# CURRENT_MEASURE_AC.net
KiCad netlist of a schematic drawn in Altium Designer
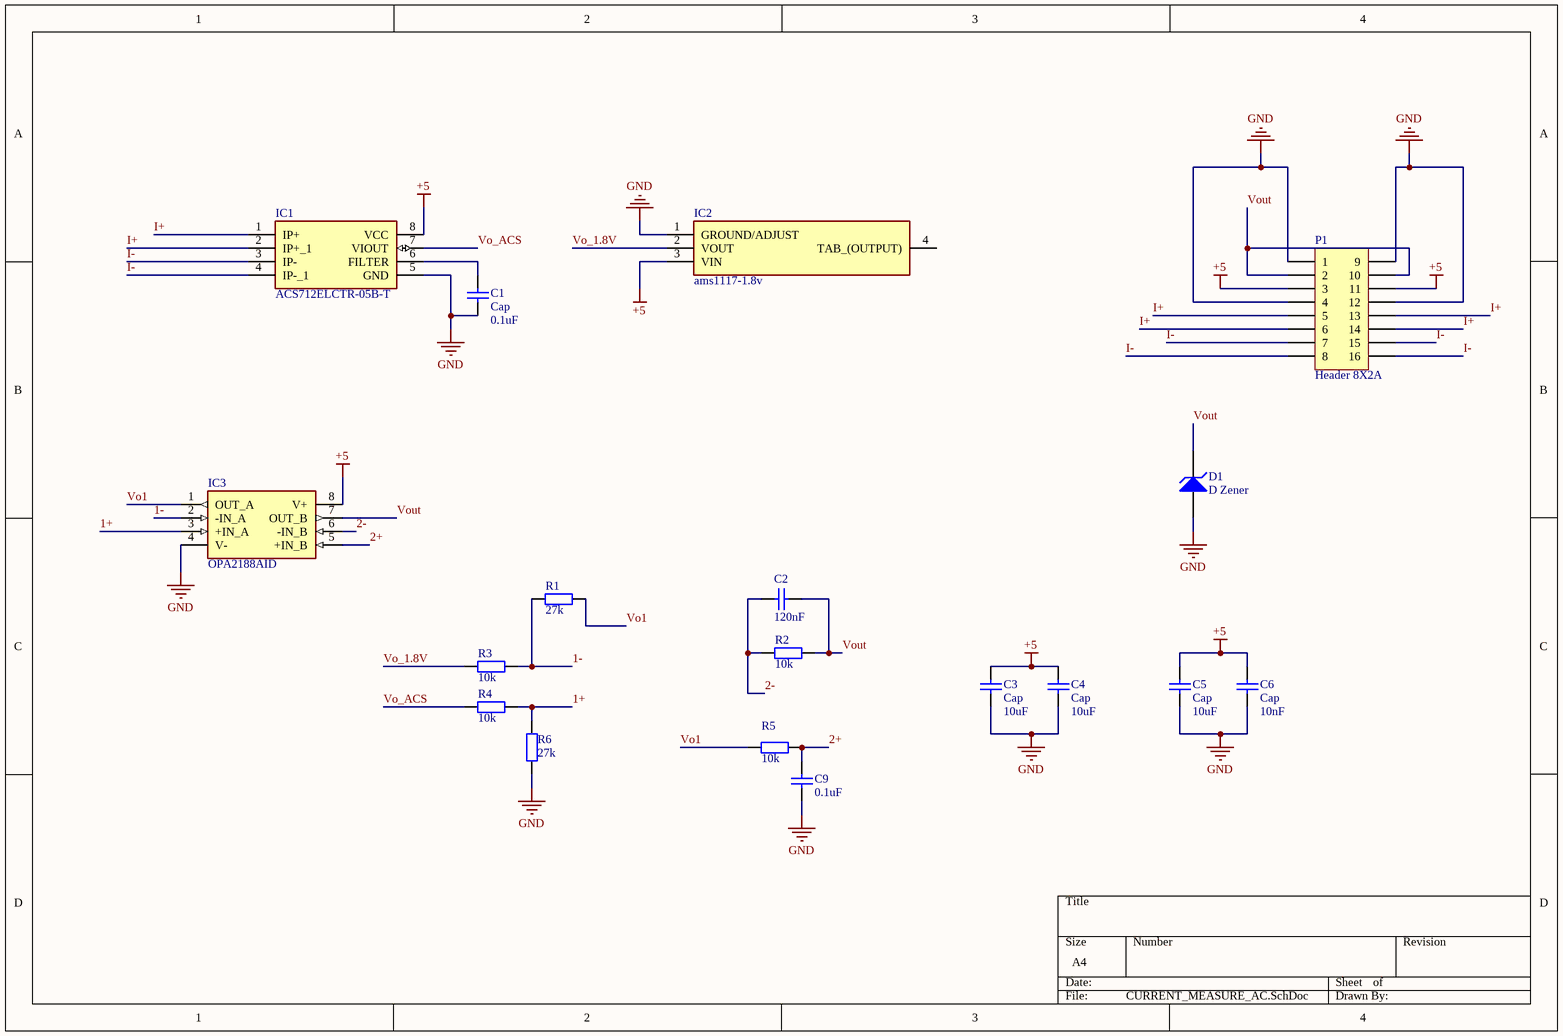
[diagram p0: CURRENT_MEASURE_AC.SchDoc]

(export (version "E")
  (design (tool "Eeschema 10.0.6"))
  (components
    (comp (ref "C1")
      (value "Cap")
      (footprint "1608[0603]")
      (description "Capacitor")
      (fields (field (name "ALTIUM_VALUE") "0.1uF") (field (name "PUBLISHER") "Altium Limited"))
      (libsource (lib "Miscellaneous Devices") (part "Cap"))
    )
    (comp (ref "C2")
      (value "120nF")
      (footprint "1608[0603]")
      (description "Capacitor")
      (fields (field (name "Comment") "Cap") (field (name "PUBLISHER") "Altium Limited"))
      (libsource (lib "Miscellaneous Devices") (part "Cap"))
    )
    (comp (ref "C3")
      (value "Cap")
      (footprint "1608[0603]")
      (description "Capacitor")
      (fields (field (name "ALTIUM_VALUE") "10uF") (field (name "PUBLISHER") "Altium Limited"))
      (libsource (lib "Miscellaneous Devices") (part "Cap"))
    )
    (comp (ref "C4")
      (value "Cap")
      (footprint "1608[0603]")
      (description "Capacitor")
      (fields (field (name "ALTIUM_VALUE") "10uF") (field (name "PUBLISHER") "Altium Limited"))
      (libsource (lib "Miscellaneous Devices") (part "Cap"))
    )
    (comp (ref "C5")
      (value "Cap")
      (footprint "1608[0603]")
      (description "Capacitor")
      (fields (field (name "ALTIUM_VALUE") "10uF") (field (name "PUBLISHER") "Altium Limited"))
      (libsource (lib "Miscellaneous Devices") (part "Cap"))
    )
    (comp (ref "C6")
      (value "Cap")
      (footprint "1608[0603]")
      (description "Capacitor")
      (fields (field (name "ALTIUM_VALUE") "10nF") (field (name "PUBLISHER") "Altium Limited"))
      (libsource (lib "Miscellaneous Devices") (part "Cap"))
    )
    (comp (ref "C9")
      (value "0.1uF")
      (footprint "1608[0603]")
      (description "Capacitor")
      (fields (field (name "Comment") "Cap") (field (name "PUBLISHER") "Altium Limited"))
      (libsource (lib "Miscellaneous Devices") (part "Cap"))
    )
    (comp (ref "D1")
      (value "D Zener")
      (footprint "C1206")
      (description "Zener Diode")
      (fields (field (name "PUBLISHER") "Altium Limited"))
      (libsource (lib "Miscellaneous Devices") (part "D Zener"))
    )
    (comp (ref "IC1")
      (value "ACS712ELCTR-05B-T")
      (footprint "SamacSys:SOIC127P600X175-8N")
      (description "Integrated Circuit")
      (fields (field (name "RS PART NUMBER") "1729270"))
      (libsource (lib "SamacSys") (part "ACS712ELCTR-05B-T"))
    )
    (comp (ref "IC2")
      (value "ams1117-1.8v")
      (footprint "SamacSys:SOT229P700X180-4N")
      (description "Integrated Circuit")
      (fields (field (name "MANUFACTURER_PART_NUMBER") "ams1117-3.3v"))
      (libsource (lib "*") (part "ams1117-3.3v"))
    )
    (comp (ref "IC3")
      (value "OPA2188AID")
      (footprint "SamacSys:SOIC127P600X175-8N")
      (description "Integrated Circuit")
      (fields (field (name "MOUSER PART NUMBER") "595-OPA2188AID") (field (name "RS PART NUMBER") "9212845"))
      (libsource (lib "SamacSys") (part "OPA2188AID"))
    )
    (comp (ref "P1")
      (value "Header 8X2A")
      (footprint "HDR2X8_CEN")
      (description "Header, 8-Pin, Dual row")
      (fields (field (name "PUBLISHER") "Altium Limited"))
      (libsource (lib "Miscellaneous Connectors") (part "Header 8X2A"))
    )
    (comp (ref "R1")
      (value "27k")
      (footprint "1608[0603]")
      (description "Resistor")
      (fields (field (name "Comment") "Res2") (field (name "PUBLISHER") "Altium Limited"))
      (libsource (lib "Miscellaneous Devices") (part "Res2"))
    )
    (comp (ref "R2")
      (value "10k")
      (footprint "1608[0603]")
      (description "Resistor")
      (fields (field (name "Comment") "Res2") (field (name "PUBLISHER") "Altium Limited"))
      (libsource (lib "Miscellaneous Devices") (part "Res2"))
    )
    (comp (ref "R3")
      (value "10k")
      (footprint "1608[0603]")
      (description "Resistor")
      (fields (field (name "Comment") "Res2") (field (name "PUBLISHER") "Altium Limited"))
      (libsource (lib "Miscellaneous Devices") (part "Res2"))
    )
    (comp (ref "R4")
      (value "10k")
      (footprint "AXIAL-0.3")
      (description "Resistor")
      (fields (field (name "Comment") "Res2") (field (name "PUBLISHER") "Altium Limited"))
      (libsource (lib "Miscellaneous Devices") (part "Res2"))
    )
    (comp (ref "R5")
      (value "10k")
      (footprint "AXIAL-0.3")
      (description "Resistor")
      (fields (field (name "Comment") "Res2") (field (name "PUBLISHER") "Altium Limited"))
      (libsource (lib "Miscellaneous Devices") (part "Res2"))
    )
    (comp (ref "R6")
      (value "27k")
      (footprint "1608[0603]")
      (description "Resistor")
      (fields (field (name "Comment") "Res2") (field (name "PUBLISHER") "Altium Limited"))
      (libsource (lib "") (part "Res2_1"))
    )
  )
  (nets
    (net (code "1") (name "+5") (class "Default")
      (node (ref "C3") (pin "2") (pinfunction "2_2") (pintype "passive"))
      (node (ref "C4") (pin "2") (pinfunction "2_2") (pintype "passive"))
      (node (ref "C5") (pin "2") (pinfunction "2_2") (pintype "passive"))
      (node (ref "C6") (pin "1") (pinfunction "1_1") (pintype "passive"))
      (node (ref "IC1") (pin "8") (pinfunction "VCC_8") (pintype "power_in"))
      (node (ref "IC2") (pin "3") (pinfunction "VIN_3") (pintype "passive"))
      (node (ref "IC3") (pin "8") (pinfunction "V+_8") (pintype "power_in"))
      (node (ref "P1") (pin "11") (pinfunction "11_11") (pintype "passive"))
      (node (ref "P1") (pin "3") (pinfunction "3_3") (pintype "passive"))
    )
    (net (code "2") (name "/1+") (class "Default")
      (node (ref "IC3") (pin "3") (pinfunction "+IN_A_3") (pintype "input"))
      (node (ref "R4") (pin "2") (pinfunction "2_2") (pintype "passive"))
      (node (ref "R6") (pin "2") (pinfunction "2_2") (pintype "passive"))
    )
    (net (code "3") (name "/1-") (class "Default")
      (node (ref "IC3") (pin "2") (pinfunction "-IN_A_2") (pintype "input"))
      (node (ref "R1") (pin "1") (pinfunction "1_1") (pintype "passive"))
      (node (ref "R3") (pin "2") (pinfunction "2_2") (pintype "passive"))
    )
    (net (code "4") (name "/2+") (class "Default")
      (node (ref "C9") (pin "2") (pinfunction "2_2") (pintype "passive"))
      (node (ref "IC3") (pin "5") (pinfunction "+IN_B_5") (pintype "input"))
      (node (ref "R5") (pin "2") (pinfunction "2_2") (pintype "passive"))
    )
    (net (code "5") (name "/2-") (class "Default")
      (node (ref "C2") (pin "1") (pinfunction "1_1") (pintype "passive"))
      (node (ref "IC3") (pin "6") (pinfunction "-IN_B_6") (pintype "input"))
      (node (ref "R2") (pin "1") (pinfunction "1_1") (pintype "passive"))
    )
    (net (code "6") (name "/I+") (class "Default")
      (node (ref "IC1") (pin "1") (pinfunction "IP+_1") (pintype "passive"))
      (node (ref "IC1") (pin "2") (pinfunction "IP+_1_2") (pintype "passive"))
      (node (ref "P1") (pin "13") (pinfunction "13_13") (pintype "passive"))
      (node (ref "P1") (pin "14") (pinfunction "14_14") (pintype "passive"))
      (node (ref "P1") (pin "5") (pinfunction "5_5") (pintype "passive"))
      (node (ref "P1") (pin "6") (pinfunction "6_6") (pintype "passive"))
    )
    (net (code "7") (name "/I-") (class "Default")
      (node (ref "IC1") (pin "3") (pinfunction "IP-_3") (pintype "passive"))
      (node (ref "IC1") (pin "4") (pinfunction "IP-_1_4") (pintype "passive"))
      (node (ref "P1") (pin "15") (pinfunction "15_15") (pintype "passive"))
      (node (ref "P1") (pin "16") (pinfunction "16_16") (pintype "passive"))
      (node (ref "P1") (pin "7") (pinfunction "7_7") (pintype "passive"))
      (node (ref "P1") (pin "8") (pinfunction "8_8") (pintype "passive"))
    )
    (net (code "8") (name "/Vo1") (class "Default")
      (node (ref "IC3") (pin "1") (pinfunction "OUT_A_1") (pintype "output"))
      (node (ref "R1") (pin "2") (pinfunction "2_2") (pintype "passive"))
      (node (ref "R5") (pin "1") (pinfunction "1_1") (pintype "passive"))
    )
    (net (code "9") (name "/Vo_1.8V") (class "Default")
      (node (ref "IC2") (pin "2") (pinfunction "VOUT_2") (pintype "passive"))
      (node (ref "R3") (pin "1") (pinfunction "1_1") (pintype "passive"))
    )
    (net (code "10") (name "/Vo_ACS") (class "Default")
      (node (ref "IC1") (pin "7") (pinfunction "VIOUT_7") (pintype "bidirectional"))
      (node (ref "R4") (pin "1") (pinfunction "1_1") (pintype "passive"))
    )
    (net (code "11") (name "/Vout") (class "Default")
      (node (ref "C2") (pin "2") (pinfunction "2_2") (pintype "passive"))
      (node (ref "D1") (pin "2") (pinfunction "K_2") (pintype "passive"))
      (node (ref "IC3") (pin "7") (pinfunction "OUT_B_7") (pintype "output"))
      (node (ref "P1") (pin "10") (pinfunction "10_10") (pintype "passive"))
      (node (ref "P1") (pin "2") (pinfunction "2_2") (pintype "passive"))
      (node (ref "R2") (pin "2") (pinfunction "2_2") (pintype "passive"))
    )
    (net (code "12") (name "GND") (class "Default")
      (node (ref "C1") (pin "2") (pinfunction "2_2") (pintype "passive"))
      (node (ref "C3") (pin "1") (pinfunction "1_1") (pintype "passive"))
      (node (ref "C4") (pin "1") (pinfunction "1_1") (pintype "passive"))
      (node (ref "C5") (pin "1") (pinfunction "1_1") (pintype "passive"))
      (node (ref "C6") (pin "2") (pinfunction "2_2") (pintype "passive"))
      (node (ref "C9") (pin "1") (pinfunction "1_1") (pintype "passive"))
      (node (ref "D1") (pin "1") (pinfunction "A_1") (pintype "passive"))
      (node (ref "IC1") (pin "5") (pinfunction "GND_5") (pintype "power_in"))
      (node (ref "IC2") (pin "1") (pinfunction "GROUND/ADJUST_1") (pintype "passive"))
      (node (ref "IC3") (pin "4") (pinfunction "V-_4") (pintype "power_in"))
      (node (ref "P1") (pin "1") (pinfunction "1_1") (pintype "passive"))
      (node (ref "P1") (pin "12") (pinfunction "12_12") (pintype "passive"))
      (node (ref "P1") (pin "4") (pinfunction "4_4") (pintype "passive"))
      (node (ref "P1") (pin "9") (pinfunction "9_9") (pintype "passive"))
      (node (ref "R6") (pin "1") (pinfunction "1_1") (pintype "passive"))
    )
    (net (code "13") (name "Net-(IC1-FILTER)") (class "Default")
      (node (ref "C1") (pin "1") (pinfunction "1_1") (pintype "passive"))
      (node (ref "IC1") (pin "6") (pinfunction "FILTER_6") (pintype "passive"))
    )
    (net (code "14") (name "unconnected-(IC2-TAB_(OUTPUT)-Pad4)") (class "Default")
      (node (ref "IC2") (pin "4") (pinfunction "TAB_(OUTPUT)_4") (pintype "passive"))
    )
  )
)
